# Schematic.net
KiCad netlist of a schematic drawn in Altium Designer
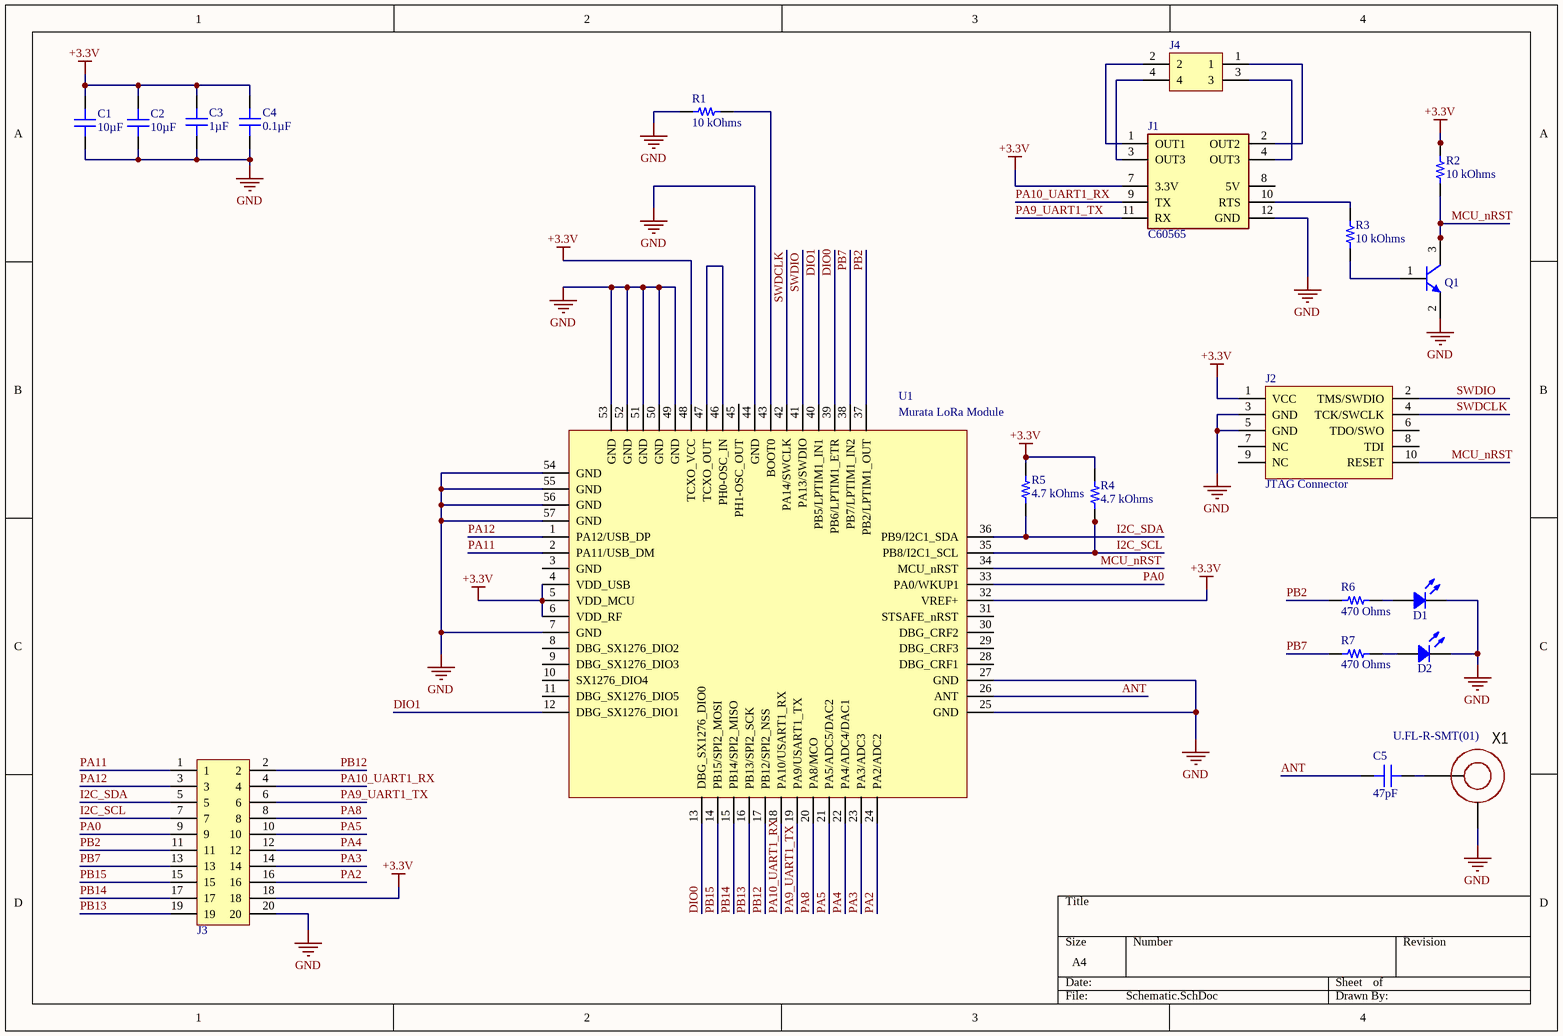
[diagram p0: Schematic.SchDoc]

(export (version "E")
  (design (tool "Eeschema 10.0.6"))
  (components
    (comp (ref "C1")
      (value "10µF")
      (footprint "CAP 0603_1608")
      (description "CAP CER 10UF 6.3V X5R 0603")
      (fields
        (field (name "MANUFACTURER") "Murata Electronics")
        (field (name "PART NUMBER") "GRM188R60J106ME47D")
      )
      (libsource (lib "Celestial") (part "Capacitor"))
    )
    (comp (ref "C2")
      (value "10µF")
      (footprint "CAP 0603_1608")
      (description "CAP CER 10UF 6.3V X5R 0603")
      (fields
        (field (name "MANUFACTURER") "Murata Electronics")
        (field (name "PART NUMBER") "GRM188R60J106ME47D")
      )
      (libsource (lib "Celestial") (part "Capacitor"))
    )
    (comp (ref "C3")
      (value "1µF")
      (footprint "CAP 0603_1608")
      (description "CAP CER 1UF 16V X7R 0603")
      (fields
        (field (name "MANUFACTURER") "Murata Electronics")
        (field (name "PART NUMBER") "GCM188R71C105KA64D")
      )
      (libsource (lib "Celestial") (part "Capacitor"))
    )
    (comp (ref "C4")
      (value "0.1µF")
      (footprint "CAP 0603_1608")
      (description "CAP CER 0.1UF 16V X7R 0603")
      (fields
        (field (name "MANUFACTURER") "Murata Electronics")
        (field (name "PART NUMBER") "GCJ188R71C104KA01D")
      )
      (libsource (lib "Celestial") (part "Capacitor"))
    )
    (comp (ref "C5")
      (value "47pF")
      (footprint "CAP 0603_1608")
      (description "CAP CER 47PF 100V C0G/NP0 0603")
      (fields
        (field (name "MANUFACTURER") "Murata Electronics")
        (field (name "PART NUMBER") "GCM1885C2A470FA16D")
      )
      (libsource (lib "Celestial") (part "Capacitor"))
    )
    (comp (ref "D1")
      (value "Green")
      (footprint "LED 0603_1608 GREEN")
      (description "LED GREEN CLEAR CHIP SMD")
      (fields (field (name "MANUFACTURER") "Kingbright") (field (name "PART NUMBER") "APT1608CGCK"))
      (libsource (lib "Celestial") (part "LED"))
    )
    (comp (ref "D2")
      (value "Red")
      (footprint "LED 0603_1608 RED")
      (description "LED RED CLEAR CHIP SMD")
      (fields (field (name "MANUFACTURER") "Kingbright") (field (name "PART NUMBER") "APT1608EC"))
      (libsource (lib "Celestial") (part "LED"))
    )
    (comp (ref "J1")
      (value "C60565")
      (footprint "C60565")
      (description "Pin Header 12 2 right-angle，90degrees 2.54mm P=2.54mm Pin Header & Female Header RoHS")
      (fields
        (field (name "MF") "Global Connector Technology")
        (field (name "MP") "BG040-14-A-0300-0300-N-G")
      )
      (libsource (lib "WB-Connector") (part "C60565"))
    )
    (comp (ref "J2")
      (value "JTAG Connector")
      (footprint "2x1.27x10")
      (libsource (lib "Misc") (part "JTAG Connector"))
    )
    (comp (ref "J3") (value "GPIO") (footprint "1.27x20") (libsource (lib "Misc") (part "GPIO")))
    (comp (ref "J4") (value "Pins") (footprint "1.27x4") (libsource (lib "Misc") (part "Pins")))
    (comp (ref "Q1")
      (value "BC847CLT1G")
      (footprint "ON SEMI SOT-23-3")
      (description "TRANS NPN 45V 0.1A SOT23")
      (fields (field (name "MANUFACTURER") "ON Semiconductor"))
      (libsource (lib "Celestial") (part "ON SEMI NPN SOT-23-3"))
    )
    (comp (ref "R1")
      (value "10 kOhms")
      (footprint "RES 0603_1608")
      (description "RES SMD 10K OHM 0.5% 1/10W 0603")
      (fields (field (name "MANUFACTURER") "Yageo") (field (name "PART NUMBER") "RT0603DRD0710KL"))
      (libsource (lib "Celestial") (part "Resistor"))
    )
    (comp (ref "R2")
      (value "10 kOhms")
      (footprint "RES 0603_1608")
      (description "RES SMD 10K OHM 0.5% 1/10W 0603")
      (fields (field (name "PART NUMBER") "RT0603DRD0710KL") (field (name "MANUFACTURER") "Yageo"))
      (libsource (lib "Celestial") (part "Resistor"))
    )
    (comp (ref "R3")
      (value "10 kOhms")
      (footprint "RES 0603_1608")
      (description "RES SMD 10K OHM 0.5% 1/10W 0603")
      (fields (field (name "PART NUMBER") "RT0603DRD0710KL") (field (name "MANUFACTURER") "Yageo"))
      (libsource (lib "Celestial") (part "Resistor"))
    )
    (comp (ref "R4")
      (value "4.7 kOhms")
      (footprint "RES 0603_1608")
      (description "RES SMD 4.7K OHM 0.1% 1/10W 0603")
      (fields (field (name "PART NUMBER") "AT0603BRD074K7L") (field (name "MANUFACTURER") "Yageo"))
      (libsource (lib "Celestial") (part "Resistor"))
    )
    (comp (ref "R5")
      (value "4.7 kOhms")
      (footprint "RES 0603_1608")
      (description "RES SMD 4.7K OHM 0.1% 1/10W 0603")
      (fields (field (name "PART NUMBER") "AT0603BRD074K7L") (field (name "MANUFACTURER") "Yageo"))
      (libsource (lib "Celestial") (part "Resistor"))
    )
    (comp (ref "R6")
      (value "470 Ohms")
      (footprint "RES 0603_1608")
      (description "RES SMD 470 OHM 1% 1/10W 0603")
      (fields (field (name "PART NUMBER") "AT0603FRE07470RL") (field (name "MANUFACTURER") "Yageo"))
      (libsource (lib "Celestial") (part "Resistor"))
    )
    (comp (ref "R7")
      (value "470 Ohms")
      (footprint "RES 0603_1608")
      (description "RES SMD 470 OHM 1% 1/10W 0603")
      (fields (field (name "PART NUMBER") "AT0603FRE07470RL") (field (name "MANUFACTURER") "Yageo"))
      (libsource (lib "Celestial") (part "Resistor"))
    )
    (comp (ref "U1")
      (value "Murata LoRa Module")
      (footprint "CMWX1ZZABZ")
      (fields (field (name "MANUFACTURER") "Murata") (field (name "PROVIDED BY") "Murata"))
      (libsource (lib "CMWX1ZZABZ") (part "CMWX1ZZABZ-078"))
    )
    (comp (ref "X1")
      (value "U.FL-R-SMT(01)")
      (footprint "CON: u.Fl")
      (description "Connector u.FL")
      (fields
        (field (name "MANUFACTURER") "Hirose Electric")
        (field (name "VALUEMANUFACTURERPARTNUMBER") "Connector u.FL, 50 Ohm, 6GHz")
      )
      (libsource (lib "Misc") (part "Connector_uFL"))
    )
  )
  (nets
    (net (code "1") (name "+3.3V") (class "Default")
      (node (ref "C1") (pin "1") (pinfunction "1_1") (pintype "passive"))
      (node (ref "C2") (pin "1") (pinfunction "1_1") (pintype "passive"))
      (node (ref "C3") (pin "1") (pinfunction "1_1") (pintype "passive"))
      (node (ref "C4") (pin "2") (pinfunction "2_2") (pintype "passive"))
      (node (ref "J1") (pin "7") (pinfunction "3.3V_7") (pintype "passive"))
      (node (ref "J2") (pin "1") (pinfunction "VCC_1") (pintype "passive"))
      (node (ref "J3") (pin "18") (pinfunction "18_18") (pintype "passive"))
      (node (ref "R2") (pin "1") (pinfunction "1_1") (pintype "passive"))
      (node (ref "R4") (pin "2") (pinfunction "2_2") (pintype "passive"))
      (node (ref "R5") (pin "2") (pinfunction "2_2") (pintype "passive"))
      (node (ref "U1") (pin "32") (pinfunction "VREF+_32") (pintype "passive"))
      (node (ref "U1") (pin "4") (pinfunction "VDD_USB_4") (pintype "passive"))
      (node (ref "U1") (pin "48") (pinfunction "TCXO_VCC_48") (pintype "passive"))
      (node (ref "U1") (pin "5") (pinfunction "VDD_MCU_5") (pintype "passive"))
      (node (ref "U1") (pin "6") (pinfunction "VDD_RF_6") (pintype "passive"))
    )
    (net (code "2") (name "/ANT") (class "Default")
      (node (ref "C5") (pin "1") (pinfunction "1_1") (pintype "passive"))
      (node (ref "U1") (pin "26") (pinfunction "ANT_26") (pintype "passive"))
    )
    (net (code "3") (name "/DIO0") (class "Default")
      (node (ref "U1") (pin "13") (pinfunction "DBG_SX1276_DIO0_13") (pintype "passive"))
      (node (ref "U1") (pin "39") (pinfunction "PB6/LPTIM1_ETR_39") (pintype "passive"))
    )
    (net (code "4") (name "/DIO1") (class "Default")
      (node (ref "U1") (pin "12") (pinfunction "DBG_SX1276_DIO1_12") (pintype "passive"))
      (node (ref "U1") (pin "40") (pinfunction "PB5/LPTIM1_IN1_40") (pintype "passive"))
    )
    (net (code "5") (name "/I2C_SCL") (class "Default")
      (node (ref "J3") (pin "7") (pinfunction "7_7") (pintype "passive"))
      (node (ref "R4") (pin "1") (pinfunction "1_1") (pintype "passive"))
      (node (ref "U1") (pin "35") (pinfunction "PB8/I2C1_SCL_35") (pintype "passive"))
    )
    (net (code "6") (name "/I2C_SDA") (class "Default")
      (node (ref "J3") (pin "5") (pinfunction "5_5") (pintype "passive"))
      (node (ref "R5") (pin "1") (pinfunction "1_1") (pintype "passive"))
      (node (ref "U1") (pin "36") (pinfunction "PB9/I2C1_SDA_36") (pintype "passive"))
    )
    (net (code "7") (name "/MCU_nRST") (class "Default")
      (node (ref "J2") (pin "10") (pinfunction "RESET_10") (pintype "passive"))
      (node (ref "Q1") (pin "3") (pinfunction "C_3") (pintype "passive"))
      (node (ref "R2") (pin "2") (pinfunction "2_2") (pintype "passive"))
      (node (ref "U1") (pin "34") (pinfunction "MCU_nRST_34") (pintype "passive"))
    )
    (net (code "8") (name "/PA0") (class "Default")
      (node (ref "J3") (pin "9") (pinfunction "9_9") (pintype "passive"))
      (node (ref "U1") (pin "33") (pinfunction "PA0/WKUP1_33") (pintype "passive"))
    )
    (net (code "9") (name "/PA2") (class "Default")
      (node (ref "J3") (pin "16") (pinfunction "16_16") (pintype "passive"))
      (node (ref "U1") (pin "24") (pinfunction "PA2/ADC2_24") (pintype "passive"))
    )
    (net (code "10") (name "/PA3") (class "Default")
      (node (ref "J3") (pin "14") (pinfunction "14_14") (pintype "passive"))
      (node (ref "U1") (pin "23") (pinfunction "PA3/ADC3_23") (pintype "passive"))
    )
    (net (code "11") (name "/PA4") (class "Default")
      (node (ref "J3") (pin "12") (pinfunction "12_12") (pintype "passive"))
      (node (ref "U1") (pin "22") (pinfunction "PA4/ADC4/DAC1_22") (pintype "passive"))
    )
    (net (code "12") (name "/PA5") (class "Default")
      (node (ref "J3") (pin "10") (pinfunction "10_10") (pintype "passive"))
      (node (ref "U1") (pin "21") (pinfunction "PA5/ADC5/DAC2_21") (pintype "passive"))
    )
    (net (code "13") (name "/PA8") (class "Default")
      (node (ref "J3") (pin "8") (pinfunction "8_8") (pintype "passive"))
      (node (ref "U1") (pin "20") (pinfunction "PA8/MCO_20") (pintype "passive"))
    )
    (net (code "14") (name "/PA9_UART1_TX") (class "Default")
      (node (ref "J1") (pin "11") (pinfunction "RX_11") (pintype "passive"))
      (node (ref "J3") (pin "6") (pinfunction "6_6") (pintype "passive"))
      (node (ref "U1") (pin "19") (pinfunction "PA9/USART1_TX_19") (pintype "passive"))
    )
    (net (code "15") (name "/PA10_UART1_RX") (class "Default")
      (node (ref "J1") (pin "9") (pinfunction "TX_9") (pintype "passive"))
      (node (ref "J3") (pin "4") (pinfunction "4_4") (pintype "passive"))
      (node (ref "U1") (pin "18") (pinfunction "PA10/USART1_RX_18") (pintype "passive"))
    )
    (net (code "16") (name "/PA11") (class "Default")
      (node (ref "J3") (pin "1") (pinfunction "1_1") (pintype "passive"))
      (node (ref "U1") (pin "2") (pinfunction "PA11/USB_DM_2") (pintype "passive"))
    )
    (net (code "17") (name "/PA12") (class "Default")
      (node (ref "J3") (pin "3") (pinfunction "3_3") (pintype "passive"))
      (node (ref "U1") (pin "1") (pinfunction "PA12/USB_DP_1") (pintype "passive"))
    )
    (net (code "18") (name "/PB2") (class "Default")
      (node (ref "J3") (pin "11") (pinfunction "11_11") (pintype "passive"))
      (node (ref "R6") (pin "2") (pinfunction "2_2") (pintype "passive"))
      (node (ref "U1") (pin "37") (pinfunction "PB2/LPTIM1_OUT_37") (pintype "passive"))
    )
    (net (code "19") (name "/PB7") (class "Default")
      (node (ref "J3") (pin "13") (pinfunction "13_13") (pintype "passive"))
      (node (ref "R7") (pin "2") (pinfunction "2_2") (pintype "passive"))
      (node (ref "U1") (pin "38") (pinfunction "PB7/LPTIM1_IN2_38") (pintype "passive"))
    )
    (net (code "20") (name "/PB12") (class "Default")
      (node (ref "J3") (pin "2") (pinfunction "2_2") (pintype "passive"))
      (node (ref "U1") (pin "17") (pinfunction "PB12/SPI2_NSS_17") (pintype "passive"))
    )
    (net (code "21") (name "/PB13") (class "Default")
      (node (ref "J3") (pin "19") (pinfunction "19_19") (pintype "passive"))
      (node (ref "U1") (pin "16") (pinfunction "PB13/SPI2_SCK_16") (pintype "passive"))
    )
    (net (code "22") (name "/PB14") (class "Default")
      (node (ref "J3") (pin "17") (pinfunction "17_17") (pintype "passive"))
      (node (ref "U1") (pin "15") (pinfunction "PB14/SPI2_MISO_15") (pintype "passive"))
    )
    (net (code "23") (name "/PB15") (class "Default")
      (node (ref "J3") (pin "15") (pinfunction "15_15") (pintype "passive"))
      (node (ref "U1") (pin "14") (pinfunction "PB15/SPI2_MOSI_14") (pintype "passive"))
    )
    (net (code "24") (name "/SWDCLK") (class "Default")
      (node (ref "J2") (pin "4") (pinfunction "TCK/SWCLK_4") (pintype "passive"))
      (node (ref "U1") (pin "42") (pinfunction "PA14/SWCLK_42") (pintype "passive"))
    )
    (net (code "25") (name "/SWDIO") (class "Default")
      (node (ref "J2") (pin "2") (pinfunction "TMS/SWDIO_2") (pintype "passive"))
      (node (ref "U1") (pin "41") (pinfunction "PA13/SWDIO_41") (pintype "passive"))
    )
    (net (code "26") (name "GND") (class "Default")
      (node (ref "C1") (pin "2") (pinfunction "2_2") (pintype "passive"))
      (node (ref "C2") (pin "2") (pinfunction "2_2") (pintype "passive"))
      (node (ref "C3") (pin "2") (pinfunction "2_2") (pintype "passive"))
      (node (ref "C4") (pin "1") (pinfunction "1_1") (pintype "passive"))
      (node (ref "D1") (pin "2") (pinfunction "2_2") (pintype "passive"))
      (node (ref "D2") (pin "2") (pinfunction "2_2") (pintype "passive"))
      (node (ref "J1") (pin "12") (pinfunction "GND_12") (pintype "passive"))
      (node (ref "J2") (pin "3") (pinfunction "GND_3") (pintype "passive"))
      (node (ref "J2") (pin "5") (pinfunction "GND_5") (pintype "passive"))
      (node (ref "J3") (pin "20") (pinfunction "20_20") (pintype "passive"))
      (node (ref "Q1") (pin "2") (pinfunction "E_2") (pintype "passive"))
      (node (ref "R1") (pin "2") (pinfunction "2_2") (pintype "passive"))
      (node (ref "U1") (pin "25") (pinfunction "GND_25") (pintype "passive"))
      (node (ref "U1") (pin "27") (pinfunction "GND_27") (pintype "passive"))
      (node (ref "U1") (pin "44") (pinfunction "GND_44") (pintype "passive"))
      (node (ref "U1") (pin "49") (pinfunction "GND_49") (pintype "passive"))
      (node (ref "U1") (pin "50") (pinfunction "GND_50") (pintype "passive"))
      (node (ref "U1") (pin "51") (pinfunction "GND_51") (pintype "passive"))
      (node (ref "U1") (pin "52") (pinfunction "GND_52") (pintype "passive"))
      (node (ref "U1") (pin "53") (pinfunction "GND_53") (pintype "passive"))
      (node (ref "U1") (pin "54") (pinfunction "GND_54") (pintype "passive"))
      (node (ref "U1") (pin "55") (pinfunction "GND_55") (pintype "passive"))
      (node (ref "U1") (pin "56") (pinfunction "GND_56") (pintype "passive"))
      (node (ref "U1") (pin "57") (pinfunction "GND_57") (pintype "passive"))
      (node (ref "U1") (pin "7") (pinfunction "GND_7") (pintype "passive"))
      (node (ref "X1") (pin "2") (pinfunction "2_2") (pintype "passive"))
    )
    (net (code "27") (name "Net-(C5-Pad2)") (class "Default")
      (node (ref "C5") (pin "2") (pinfunction "2_2") (pintype "passive"))
      (node (ref "X1") (pin "1") (pinfunction "1_1") (pintype "passive"))
    )
    (net (code "28") (name "Net-(D1-Pad1)") (class "Default")
      (node (ref "D1") (pin "1") (pinfunction "1_1") (pintype "passive"))
      (node (ref "R6") (pin "1") (pinfunction "1_1") (pintype "passive"))
    )
    (net (code "29") (name "Net-(D2-Pad1)") (class "Default")
      (node (ref "D2") (pin "1") (pinfunction "1_1") (pintype "passive"))
      (node (ref "R7") (pin "1") (pinfunction "1_1") (pintype "passive"))
    )
    (net (code "30") (name "Net-(J1-OUT1)") (class "Default")
      (node (ref "J1") (pin "1") (pinfunction "OUT1_1") (pintype "passive"))
      (node (ref "J4") (pin "2") (pinfunction "2_2") (pintype "passive"))
    )
    (net (code "31") (name "Net-(J1-OUT2)") (class "Default")
      (node (ref "J1") (pin "2") (pinfunction "OUT2_2") (pintype "passive"))
      (node (ref "J4") (pin "1") (pinfunction "1_1") (pintype "passive"))
    )
    (net (code "32") (name "Net-(J1-OUT3-Pad3)") (class "Default")
      (node (ref "J1") (pin "3") (pinfunction "OUT3_3") (pintype "passive"))
      (node (ref "J4") (pin "4") (pinfunction "4_4") (pintype "passive"))
    )
    (net (code "33") (name "Net-(J1-OUT3-Pad4)") (class "Default")
      (node (ref "J1") (pin "4") (pinfunction "OUT3_4") (pintype "passive"))
      (node (ref "J4") (pin "3") (pinfunction "3_3") (pintype "passive"))
    )
    (net (code "34") (name "Net-(J1-RTS)") (class "Default")
      (node (ref "J1") (pin "10") (pinfunction "RTS_10") (pintype "passive"))
      (node (ref "R3") (pin "1") (pinfunction "1_1") (pintype "passive"))
    )
    (net (code "35") (name "Net-(Q1-B)") (class "Default")
      (node (ref "Q1") (pin "1") (pinfunction "B_1") (pintype "passive"))
      (node (ref "R3") (pin "2") (pinfunction "2_2") (pintype "passive"))
    )
    (net (code "36") (name "Net-(U1-BOOT0)") (class "Default")
      (node (ref "R1") (pin "1") (pinfunction "1_1") (pintype "passive"))
      (node (ref "U1") (pin "43") (pinfunction "BOOT0_43") (pintype "passive"))
    )
    (net (code "37") (name "Net-(U1-PH0-OSC_IN)") (class "Default")
      (node (ref "U1") (pin "46") (pinfunction "PH0-OSC_IN_46") (pintype "passive"))
      (node (ref "U1") (pin "47") (pinfunction "TCXO_OUT_47") (pintype "passive"))
    )
    (net (code "38") (name "unconnected-(J1-5V-Pad8)") (class "Default")
      (node (ref "J1") (pin "8") (pinfunction "5V_8") (pintype "passive"))
    )
    (net (code "39") (name "unconnected-(J2-NC-Pad7)") (class "Default")
      (node (ref "J2") (pin "7") (pinfunction "NC_7") (pintype "passive"))
    )
    (net (code "40") (name "unconnected-(J2-NC-Pad9)") (class "Default")
      (node (ref "J2") (pin "9") (pinfunction "NC_9") (pintype "passive"))
    )
    (net (code "41") (name "unconnected-(J2-TDI-Pad8)") (class "Default")
      (node (ref "J2") (pin "8") (pinfunction "TDI_8") (pintype "passive"))
    )
    (net (code "42") (name "unconnected-(J2-TDO{slash}SWO-Pad6)") (class "Default")
      (node (ref "J2") (pin "6") (pinfunction "TDO/SWO_6") (pintype "passive"))
    )
    (net (code "43") (name "unconnected-(U1-DBG_CRF1-Pad28)") (class "Default")
      (node (ref "U1") (pin "28") (pinfunction "DBG_CRF1_28") (pintype "passive"))
    )
    (net (code "44") (name "unconnected-(U1-DBG_CRF2-Pad30)") (class "Default")
      (node (ref "U1") (pin "30") (pinfunction "DBG_CRF2_30") (pintype "passive"))
    )
    (net (code "45") (name "unconnected-(U1-DBG_CRF3-Pad29)") (class "Default")
      (node (ref "U1") (pin "29") (pinfunction "DBG_CRF3_29") (pintype "passive"))
    )
    (net (code "46") (name "unconnected-(U1-DBG_SX1276_DIO2-Pad8)") (class "Default")
      (node (ref "U1") (pin "8") (pinfunction "DBG_SX1276_DIO2_8") (pintype "passive"))
    )
    (net (code "47") (name "unconnected-(U1-DBG_SX1276_DIO3-Pad9)") (class "Default")
      (node (ref "U1") (pin "9") (pinfunction "DBG_SX1276_DIO3_9") (pintype "passive"))
    )
    (net (code "48") (name "unconnected-(U1-DBG_SX1276_DIO5-Pad11)") (class "Default")
      (node (ref "U1") (pin "11") (pinfunction "DBG_SX1276_DIO5_11") (pintype "passive"))
    )
    (net (code "49") (name "unconnected-(U1-GND-Pad3)") (class "Default")
      (node (ref "U1") (pin "3") (pinfunction "GND_3") (pintype "passive"))
    )
    (net (code "50") (name "unconnected-(U1-PH1-OSC_OUT-Pad45)") (class "Default")
      (node (ref "U1") (pin "45") (pinfunction "PH1-OSC_OUT_45") (pintype "passive"))
    )
    (net (code "51") (name "unconnected-(U1-STSAFE_nRST-Pad31)") (class "Default")
      (node (ref "U1") (pin "31") (pinfunction "STSAFE_nRST_31") (pintype "passive"))
    )
    (net (code "52") (name "unconnected-(U1-SX1276_DIO4-Pad10)") (class "Default")
      (node (ref "U1") (pin "10") (pinfunction "SX1276_DIO4_10") (pintype "passive"))
    )
  )
)
